# MCU.net
KiCad netlist of a schematic drawn in Altium Designer
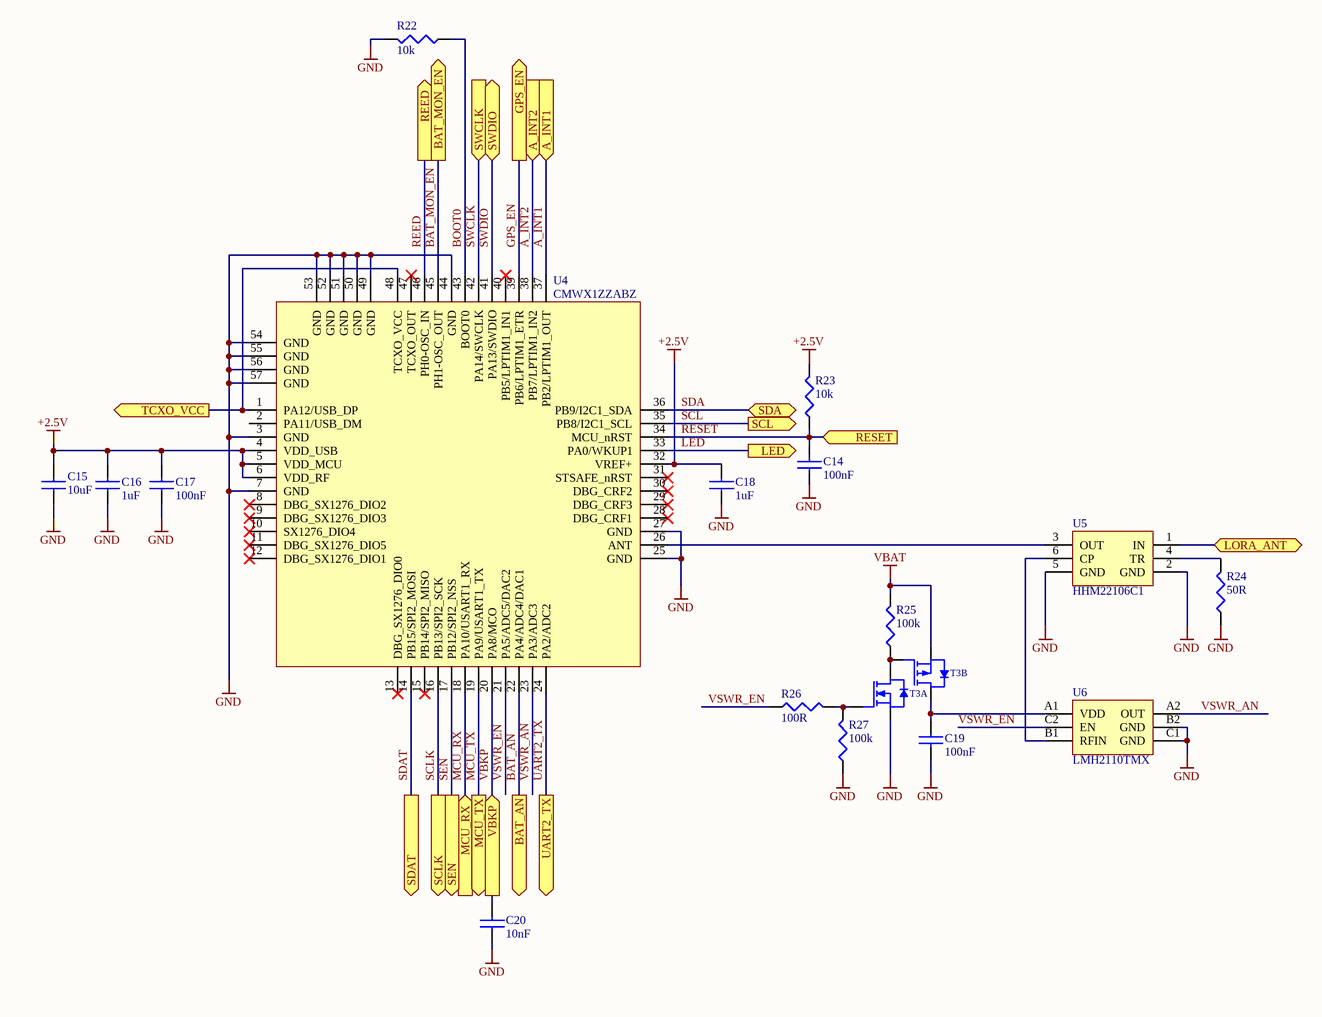
[diagram p0: MCU.SchDoc]

(export (version "E")
  (design (tool "Eeschema 10.0.6"))
  (components
    (comp (ref "C14")
      (value "100nF")
      (footprint "CAP0402")
      (fields
        (field (name "MANUFACTURER") "Multicomp")
        (field (name "MANUFACTURER PART NUMBER") "MC0402X104J160CT")
        (field (name "TOLERANCE") "5%")
      )
      (libsource (lib "Passive") (part "C - 100nF/0402"))
    )
    (comp (ref "C15")
      (value "10uF")
      (footprint "CAP0603")
      (description "10uf/0603/20%")
      (fields
        (field (name "MANUFACTURER") "KEMET")
        (field (name "MANUFACTURER PART NUMBER") "C0603C106M8PACTU")
      )
      (libsource (lib "pira-smart-schlib") (part "10uF"))
    )
    (comp (ref "C16")
      (value "1uF")
      (footprint "CAP0402")
      (description "CAP CER 1UF 10V 20% X5R 0402")
      (fields
        (field (name "MANUFACTURER") "Murata")
        (field (name "MANUFACTURER PART NUMBER") "GRM155R61A105ME15D")
      )
      (libsource (lib "Passive") (part "C - 1uF/0402"))
    )
    (comp (ref "C17")
      (value "100nF")
      (footprint "CAP0402")
      (fields
        (field (name "MANUFACTURER") "Multicomp")
        (field (name "MANUFACTURER PART NUMBER") "MC0402X104J160CT")
        (field (name "TOLERANCE") "5%")
      )
      (libsource (lib "Passive") (part "C - 100nF/0402"))
    )
    (comp (ref "C18")
      (value "1uF")
      (footprint "CAP0402")
      (description "CAP CER 1UF 10V 20% X5R 0402")
      (fields
        (field (name "MANUFACTURER") "Murata")
        (field (name "MANUFACTURER PART NUMBER") "GRM155R61A105ME15D")
      )
      (libsource (lib "Passive") (part "C - 1uF/0402"))
    )
    (comp (ref "C19")
      (value "100nF")
      (footprint "CAP0402")
      (fields
        (field (name "MANUFACTURER") "Multicomp")
        (field (name "MANUFACTURER PART NUMBER") "MC0402X104J160CT")
        (field (name "TOLERANCE") "5%")
      )
      (libsource (lib "Passive") (part "C - 100nF/0402"))
    )
    (comp (ref "C20")
      (value "10nF")
      (footprint "CAP0402")
      (description "CAP CER 10000PF 16V X7R 0402")
      (fields
        (field (name "MANUFACTURER") "Murata")
        (field (name "MANUFACTURER PART NUMBER") "GRM155R71C103KA01D")
      )
      (libsource (lib "Passive") (part "C - 10nF/0402"))
    )
    (comp (ref "R22")
      (value "10k")
      (footprint "RES0402")
      (fields
        (field (name "MANUFACTURER") "Multicomp")
        (field (name "MANUFACTURER PART NUMBER") "MCWR04X1002FTL")
        (field (name "TOLERANCE") "1%")
      )
      (libsource (lib "Passive") (part "R - 10k/0402"))
    )
    (comp (ref "R23")
      (value "10k")
      (footprint "RES0402")
      (fields
        (field (name "MANUFACTURER") "Multicomp")
        (field (name "MANUFACTURER PART NUMBER") "MCWR04X1002FTL")
        (field (name "TOLERANCE") "1%")
      )
      (libsource (lib "Passive") (part "R - 10k/0402"))
    )
    (comp (ref "R24")
      (value "50R")
      (footprint "RES0402")
      (description "SMD Chip Resistor, 0402 [1005 Metric], 50 ohm, FC Series, 30 V, Thin Film, 50 mW")
      (fields
        (field (name "MANUFACTURER") "Vishay")
        (field (name "MANUFACTURER PART NUMBER") "CRCW060351R0FKEA")
      )
      (libsource (lib "Passive") (part "R - 50R"))
    )
    (comp (ref "R25")
      (value "100k")
      (footprint "RES0402")
      (description "MULTICOMP   MCWR04X1003FTL   RES, THICK FILM, 100KOHM, 1%, 0.0625W")
      (fields
        (field (name "MANUFACTURER") "Multicomp")
        (field (name "MANUFACTURER PART NUMBER") "MCWR04X1003FTL")
      )
      (libsource (lib "Passive") (part "R - 100k/0402"))
    )
    (comp (ref "R26")
      (value "100R")
      (footprint "RES0402")
      (fields
        (field (name "MANUFACTURER") "Multicomp")
        (field (name "MANUFACTURER PART NUMBER") "MCMR04X1000FTL")
        (field (name "TOLERANCE") "1%")
      )
      (libsource (lib "Passive") (part "R - 100R/0402"))
    )
    (comp (ref "R27")
      (value "100k")
      (footprint "RES0402")
      (description "MULTICOMP   MCWR04X1003FTL   RES, THICK FILM, 100KOHM, 1%, 0.0625W")
      (fields
        (field (name "MANUFACTURER") "Multicomp")
        (field (name "MANUFACTURER PART NUMBER") "MCWR04X1003FTL")
      )
      (libsource (lib "Passive") (part "R - 100k/0402"))
    )
    (comp (ref "T3")
      (value "VT6M1T2CR")
      (footprint "VMT6")
      (description "Dual MOSFET, N and P Channel, 100 mA, 20 V, 2.5 ohm, 4.5 V, 1 V")
      (fields (field (name "AUTHOR") "Ciril Golob"))
      (libsource (lib "Active") (part "T_M - VT6M1T2CR"))
    )
    (comp (ref "U4")
      (value "CMWX1ZZABZ")
      (footprint "Lora Module ES0")
      (description "RF Module, FSK, OOK, LoRa, 4.8Kbps, 915MHz, -135.5dBm, 2.2V to 3.6V, I2C, SPI, UART, USB")
      (fields
        (field (name "MANUFACTURER") "Murata")
        (field (name "MANUFACTURER PART NUMBER") "CMWX1ZZABZ-091")
      )
      (libsource (lib "Active") (part "MCU - CMWX1ZZABZ"))
    )
    (comp (ref "U5")
      (value "HHM22106C1")
      (footprint "HHM22106C1")
      (description "Signal Conditioning DIRECTIONAL COUPLER 700-2700MHz")
      (fields (field (name "MANUFACTURER") "u-blox") (field (name "MANUFACTURER PART NUMBER") "MAX-M8Q-0"))
      (libsource (lib "Active") (part "RF - HHM22106C1"))
    )
    (comp (ref "U6")
      (value "LMH2110TMX")
      (footprint "DSBGA-6")
      (description "RF Detector IC GSM, EDGE, CDMA 50MHz ~ 8GHz -40dBm ~ 5dBm ±0,5dB")
      (fields (field (name "MANUFACTURER") "u-blox") (field (name "MANUFACTURER PART NUMBER") "MAX-M8Q-0"))
      (libsource (lib "Active") (part "RF - LMH2110TMX"))
    )
  )
  (nets
    (net (code "1") (name "+2.5V") (class "Default")
      (node (ref "C15") (pin "2") (pinfunction "2_2") (pintype "passive"))
      (node (ref "C16") (pin "2") (pinfunction "2_2") (pintype "passive"))
      (node (ref "C17") (pin "2") (pinfunction "2_2") (pintype "passive"))
      (node (ref "C18") (pin "2") (pinfunction "2_2") (pintype "passive"))
      (node (ref "R23") (pin "2") (pinfunction "2_2") (pintype "passive"))
      (node (ref "U4") (pin "32") (pinfunction "VREF+_32") (pintype "passive"))
      (node (ref "U4") (pin "4") (pinfunction "VDD_USB_4") (pintype "passive"))
      (node (ref "U4") (pin "5") (pinfunction "VDD_MCU_5") (pintype "passive"))
      (node (ref "U4") (pin "6") (pinfunction "VDD_RF_6") (pintype "passive"))
    )
    (net (code "2") (name "/A_INT1") (class "Default")
      (node (ref "U4") (pin "37") (pinfunction "PB2/LPTIM1_OUT_37") (pintype "passive"))
    )
    (net (code "3") (name "/A_INT2") (class "Default")
      (node (ref "U4") (pin "38") (pinfunction "PB7/LPTIM1_IN2_38") (pintype "passive"))
    )
    (net (code "4") (name "/BAT_AN") (class "Default")
      (node (ref "U4") (pin "22") (pinfunction "PA4/ADC4/DAC1_22") (pintype "passive"))
    )
    (net (code "5") (name "/BAT_MON_EN") (class "Default")
      (node (ref "U4") (pin "45") (pinfunction "PH1-OSC_OUT_45") (pintype "passive"))
    )
    (net (code "6") (name "/BOOT0") (class "Default")
      (node (ref "R22") (pin "1") (pinfunction "1_1") (pintype "passive"))
      (node (ref "U4") (pin "43") (pinfunction "BOOT0_43") (pintype "passive"))
    )
    (net (code "7") (name "/GPS_EN") (class "Default")
      (node (ref "U4") (pin "39") (pinfunction "PB6/LPTIM1_ETR_39") (pintype "passive"))
    )
    (net (code "8") (name "/LED") (class "Default")
      (node (ref "U4") (pin "33") (pinfunction "PA0/WKUP1_33") (pintype "passive"))
    )
    (net (code "9") (name "/LORA_ANT") (class "Default")
      (node (ref "U5") (pin "1") (pinfunction "IN_1") (pintype "passive"))
    )
    (net (code "10") (name "/MCU_RX") (class "Default")
      (node (ref "U4") (pin "18") (pinfunction "PA10/USART1_RX_18") (pintype "passive"))
    )
    (net (code "11") (name "/MCU_TX") (class "Default")
      (node (ref "U4") (pin "19") (pinfunction "PA9/USART1_TX_19") (pintype "passive"))
    )
    (net (code "12") (name "/REED") (class "Default")
      (node (ref "U4") (pin "46") (pinfunction "PH0-OSC_IN_46") (pintype "passive"))
    )
    (net (code "13") (name "/RESET") (class "Default")
      (node (ref "C14") (pin "2") (pinfunction "2_2") (pintype "passive"))
      (node (ref "R23") (pin "1") (pinfunction "1_1") (pintype "passive"))
      (node (ref "U4") (pin "34") (pinfunction "MCU_nRST_34") (pintype "passive"))
    )
    (net (code "14") (name "/SCL") (class "Default")
      (node (ref "U4") (pin "35") (pinfunction "PB8/I2C1_SCL_35") (pintype "passive"))
    )
    (net (code "15") (name "/SCLK") (class "Default")
      (node (ref "U4") (pin "16") (pinfunction "PB13/SPI2_SCK_16") (pintype "passive"))
    )
    (net (code "16") (name "/SDA") (class "Default")
      (node (ref "U4") (pin "36") (pinfunction "PB9/I2C1_SDA_36") (pintype "passive"))
    )
    (net (code "17") (name "/SDAT") (class "Default")
      (node (ref "U4") (pin "14") (pinfunction "PB15/SPI2_MOSI_14") (pintype "passive"))
    )
    (net (code "18") (name "/SEN") (class "Default")
      (node (ref "U4") (pin "17") (pinfunction "PB12/SPI2_NSS_17") (pintype "passive"))
    )
    (net (code "19") (name "/SWCLK") (class "Default")
      (node (ref "U4") (pin "42") (pinfunction "PA14/SWCLK_42") (pintype "passive"))
    )
    (net (code "20") (name "/SWDIO") (class "Default")
      (node (ref "U4") (pin "41") (pinfunction "PA13/SWDIO_41") (pintype "passive"))
    )
    (net (code "21") (name "/TCXO_VCC") (class "Default")
      (node (ref "U4") (pin "1") (pinfunction "PA12/USB_DP_1") (pintype "passive"))
      (node (ref "U4") (pin "48") (pinfunction "TCXO_VCC_48") (pintype "passive"))
    )
    (net (code "22") (name "/UART2_TX") (class "Default")
      (node (ref "U4") (pin "24") (pinfunction "PA2/ADC2_24") (pintype "passive"))
    )
    (net (code "23") (name "/VBKP") (class "Default")
      (node (ref "C20") (pin "2") (pinfunction "2_2") (pintype "passive"))
      (node (ref "U4") (pin "20") (pinfunction "PA8/MCO_20") (pintype "passive"))
    )
    (net (code "24") (name "/VSWR_AN") (class "Default")
      (node (ref "U4") (pin "23") (pinfunction "PA3/ADC3_23") (pintype "passive"))
      (node (ref "U6") (pin "A2") (pinfunction "OUT_A2") (pintype "passive"))
    )
    (net (code "25") (name "/VSWR_EN") (class "Default")
      (node (ref "R26") (pin "1") (pinfunction "1_1") (pintype "passive"))
      (node (ref "U4") (pin "21") (pinfunction "PA5/ADC5/DAC2_21") (pintype "passive"))
      (node (ref "U6") (pin "C2") (pinfunction "EN_C2") (pintype "passive"))
    )
    (net (code "26") (name "GND") (class "Default")
      (node (ref "C14") (pin "1") (pinfunction "1_1") (pintype "passive"))
      (node (ref "C15") (pin "1") (pinfunction "1_1") (pintype "passive"))
      (node (ref "C16") (pin "1") (pinfunction "1_1") (pintype "passive"))
      (node (ref "C17") (pin "1") (pinfunction "1_1") (pintype "passive"))
      (node (ref "C18") (pin "1") (pinfunction "1_1") (pintype "passive"))
      (node (ref "C19") (pin "2") (pinfunction "2_2") (pintype "passive"))
      (node (ref "C20") (pin "1") (pinfunction "1_1") (pintype "passive"))
      (node (ref "R22") (pin "2") (pinfunction "2_2") (pintype "passive"))
      (node (ref "R24") (pin "1") (pinfunction "1_1") (pintype "passive"))
      (node (ref "R27") (pin "1") (pinfunction "1_1") (pintype "passive"))
      (node (ref "T3") (pin "1") (pinfunction "S1_1") (pintype "passive"))
      (node (ref "U4") (pin "25") (pinfunction "GND_25") (pintype "passive"))
      (node (ref "U4") (pin "27") (pinfunction "GND_27") (pintype "passive"))
      (node (ref "U4") (pin "3") (pinfunction "GND_3") (pintype "passive"))
      (node (ref "U4") (pin "44") (pinfunction "GND_44") (pintype "passive"))
      (node (ref "U4") (pin "49") (pinfunction "GND_49") (pintype "passive"))
      (node (ref "U4") (pin "50") (pinfunction "GND_50") (pintype "passive"))
      (node (ref "U4") (pin "51") (pinfunction "GND_51") (pintype "passive"))
      (node (ref "U4") (pin "52") (pinfunction "GND_52") (pintype "passive"))
      (node (ref "U4") (pin "53") (pinfunction "GND_53") (pintype "passive"))
      (node (ref "U4") (pin "54") (pinfunction "GND_54") (pintype "passive"))
      (node (ref "U4") (pin "55") (pinfunction "GND_55") (pintype "passive"))
      (node (ref "U4") (pin "56") (pinfunction "GND_56") (pintype "passive"))
      (node (ref "U4") (pin "57") (pinfunction "GND_57") (pintype "passive"))
      (node (ref "U4") (pin "7") (pinfunction "GND_7") (pintype "passive"))
      (node (ref "U5") (pin "2") (pinfunction "GND_2") (pintype "passive"))
      (node (ref "U5") (pin "5") (pinfunction "GND_5") (pintype "passive"))
      (node (ref "U6") (pin "B2") (pinfunction "GND_B2") (pintype "passive"))
      (node (ref "U6") (pin "C1") (pinfunction "GND_C1") (pintype "passive"))
    )
    (net (code "27") (name "Net-(T3A-D1)") (class "Default")
      (node (ref "R25") (pin "1") (pinfunction "1_1") (pintype "passive"))
      (node (ref "T3") (pin "5") (pinfunction "G2_5") (pintype "passive"))
      (node (ref "T3") (pin "6") (pinfunction "D1_6") (pintype "passive"))
    )
    (net (code "28") (name "Net-(T3A-G1)") (class "Default")
      (node (ref "R26") (pin "2") (pinfunction "2_2") (pintype "passive"))
      (node (ref "R27") (pin "2") (pinfunction "2_2") (pintype "passive"))
      (node (ref "T3") (pin "2") (pinfunction "G1_2") (pintype "passive"))
    )
    (net (code "29") (name "Net-(T3B-D2)") (class "Default")
      (node (ref "C19") (pin "1") (pinfunction "1_1") (pintype "passive"))
      (node (ref "T3") (pin "3") (pinfunction "D2_3") (pintype "passive"))
      (node (ref "U6") (pin "A1") (pinfunction "VDD_A1") (pintype "passive"))
    )
    (net (code "30") (name "Net-(U4-ANT)") (class "Default")
      (node (ref "U4") (pin "26") (pinfunction "ANT_26") (pintype "passive"))
      (node (ref "U5") (pin "3") (pinfunction "OUT_3") (pintype "passive"))
    )
    (net (code "31") (name "Net-(U5-CP)") (class "Default")
      (node (ref "U5") (pin "6") (pinfunction "CP_6") (pintype "passive"))
      (node (ref "U6") (pin "B1") (pinfunction "RFIN_B1") (pintype "passive"))
    )
    (net (code "32") (name "Net-(U5-TR)") (class "Default")
      (node (ref "R24") (pin "2") (pinfunction "2_2") (pintype "passive"))
      (node (ref "U5") (pin "4") (pinfunction "TR_4") (pintype "passive"))
    )
    (net (code "33") (name "VBAT") (class "Default")
      (node (ref "R25") (pin "2") (pinfunction "2_2") (pintype "passive"))
      (node (ref "T3") (pin "4") (pinfunction "S2_4") (pintype "passive"))
    )
    (net (code "34") (name "unconnected-(U4-DBG_CRF1-Pad28)") (class "Default")
      (node (ref "U4") (pin "28") (pinfunction "DBG_CRF1_28") (pintype "passive+no_connect"))
    )
    (net (code "35") (name "unconnected-(U4-DBG_CRF2-Pad30)") (class "Default")
      (node (ref "U4") (pin "30") (pinfunction "DBG_CRF2_30") (pintype "passive+no_connect"))
    )
    (net (code "36") (name "unconnected-(U4-DBG_CRF3-Pad29)") (class "Default")
      (node (ref "U4") (pin "29") (pinfunction "DBG_CRF3_29") (pintype "passive+no_connect"))
    )
    (net (code "37") (name "unconnected-(U4-DBG_SX1276_DIO0-Pad13)") (class "Default")
      (node (ref "U4") (pin "13") (pinfunction "DBG_SX1276_DIO0_13") (pintype "passive+no_connect"))
    )
    (net (code "38") (name "unconnected-(U4-DBG_SX1276_DIO1-Pad12)") (class "Default")
      (node (ref "U4") (pin "12") (pinfunction "DBG_SX1276_DIO1_12") (pintype "passive+no_connect"))
    )
    (net (code "39") (name "unconnected-(U4-DBG_SX1276_DIO2-Pad8)") (class "Default")
      (node (ref "U4") (pin "8") (pinfunction "DBG_SX1276_DIO2_8") (pintype "passive+no_connect"))
    )
    (net (code "40") (name "unconnected-(U4-DBG_SX1276_DIO3-Pad9)") (class "Default")
      (node (ref "U4") (pin "9") (pinfunction "DBG_SX1276_DIO3_9") (pintype "passive+no_connect"))
    )
    (net (code "41") (name "unconnected-(U4-DBG_SX1276_DIO5-Pad11)") (class "Default")
      (node (ref "U4") (pin "11") (pinfunction "DBG_SX1276_DIO5_11") (pintype "passive+no_connect"))
    )
    (net (code "42") (name "unconnected-(U4-PA11{slash}USB_DM-Pad2)") (class "Default")
      (node (ref "U4") (pin "2") (pinfunction "PA11/USB_DM_2") (pintype "passive"))
    )
    (net (code "43") (name "unconnected-(U4-PB5{slash}LPTIM1_IN1-Pad40)") (class "Default")
      (node (ref "U4") (pin "40") (pinfunction "PB5/LPTIM1_IN1_40") (pintype "passive+no_connect"))
    )
    (net (code "44") (name "unconnected-(U4-PB14{slash}SPI2_MISO-Pad15)") (class "Default")
      (node (ref "U4") (pin "15") (pinfunction "PB14/SPI2_MISO_15") (pintype "passive+no_connect"))
    )
    (net (code "45") (name "unconnected-(U4-STSAFE_nRST-Pad31)") (class "Default")
      (node (ref "U4") (pin "31") (pinfunction "STSAFE_nRST_31") (pintype "passive+no_connect"))
    )
    (net (code "46") (name "unconnected-(U4-SX1276_DIO4-Pad10)") (class "Default")
      (node (ref "U4") (pin "10") (pinfunction "SX1276_DIO4_10") (pintype "passive+no_connect"))
    )
    (net (code "47") (name "unconnected-(U4-TCXO_OUT-Pad47)") (class "Default")
      (node (ref "U4") (pin "47") (pinfunction "TCXO_OUT_47") (pintype "passive+no_connect"))
    )
  )
)
